# TC.net
KiCad netlist of a schematic drawn in Altium Designer
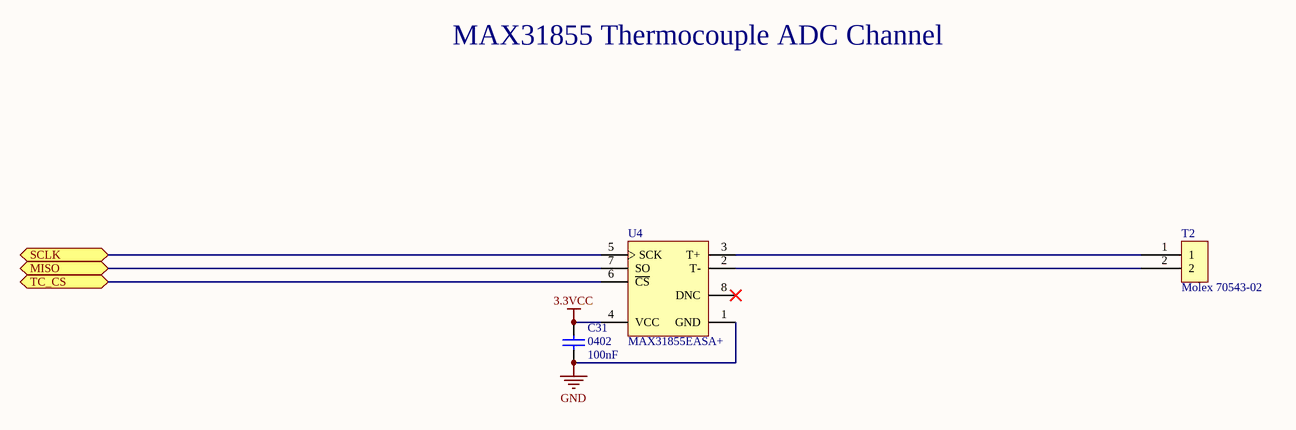
[diagram p0: TC.SchDoc]

(export (version "E")
  (design (tool "Eeschema 10.0.6"))
  (components
    (comp (ref "C31")
      (value "100nF")
      (footprint "C0402")
      (description "Capacitor (Semiconductor SIM Model)")
      (fields
        (field (name "MFR PART #") "GRM155R71C104KA88D")
        (field (name "MFR") "Murata")
        (field (name "PACKAGEREFERENCE") "0402")
        (field (name "PUBLISHER") "Ultimachine")
      )
      (libsource (lib "Tigershark3D") (part "100nF C0402 - GRM155R71C104KA88D"))
    )
    (comp (ref "T2")
      (value "Molex 70543-02")
      (footprint "70543-02")
      (libsource (lib "ZMBo Schematic Library") (part "Molex 70543-02"))
    )
    (comp (ref "U4")
      (value "MAX31855EASA+")
      (footprint "MAXM-S8+4_N")
      (fields (field (name "GENERIC PART NUMBER") "MAX31855"))
      (libsource (lib "Maxim Sensors") (part "MAX31855EASA+"))
    )
  )
  (nets
    (net (code "1") (name "/MISO") (class "Default")
      (node (ref "U4") (pin "7") (pinfunction "SO_7") (pintype "passive"))
    )
    (net (code "2") (name "/SCLK") (class "Default")
      (node (ref "U4") (pin "5") (pinfunction "SCK_5") (pintype "passive"))
    )
    (net (code "3") (name "/TC_CS") (class "Default")
      (node (ref "U4") (pin "6") (pinfunction "~{CS}_6") (pintype "passive"))
    )
    (net (code "4") (name "3.3VCC") (class "Default")
      (node (ref "C31") (pin "2") (pinfunction "2_2") (pintype "passive"))
      (node (ref "U4") (pin "4") (pinfunction "VCC_4") (pintype "power_in"))
    )
    (net (code "5") (name "GND") (class "Default")
      (node (ref "C31") (pin "1") (pinfunction "1_1") (pintype "passive"))
      (node (ref "U4") (pin "1") (pinfunction "GND_1") (pintype "passive"))
    )
    (net (code "6") (name "Net-(U4-T+)") (class "Default")
      (node (ref "T2") (pin "1") (pinfunction "1_1") (pintype "passive"))
      (node (ref "U4") (pin "3") (pinfunction "T+_3") (pintype "passive"))
    )
    (net (code "7") (name "Net-(U4-T-)") (class "Default")
      (node (ref "T2") (pin "2") (pinfunction "2_2") (pintype "passive"))
      (node (ref "U4") (pin "2") (pinfunction "T-_2") (pintype "passive"))
    )
    (net (code "8") (name "unconnected-(U4-DNC-Pad8)") (class "Default")
      (node (ref "U4") (pin "8") (pinfunction "DNC_8") (pintype "passive+no_connect"))
    )
  )
)
